# Com.net
KiCad netlist of a schematic drawn in Altium Designer
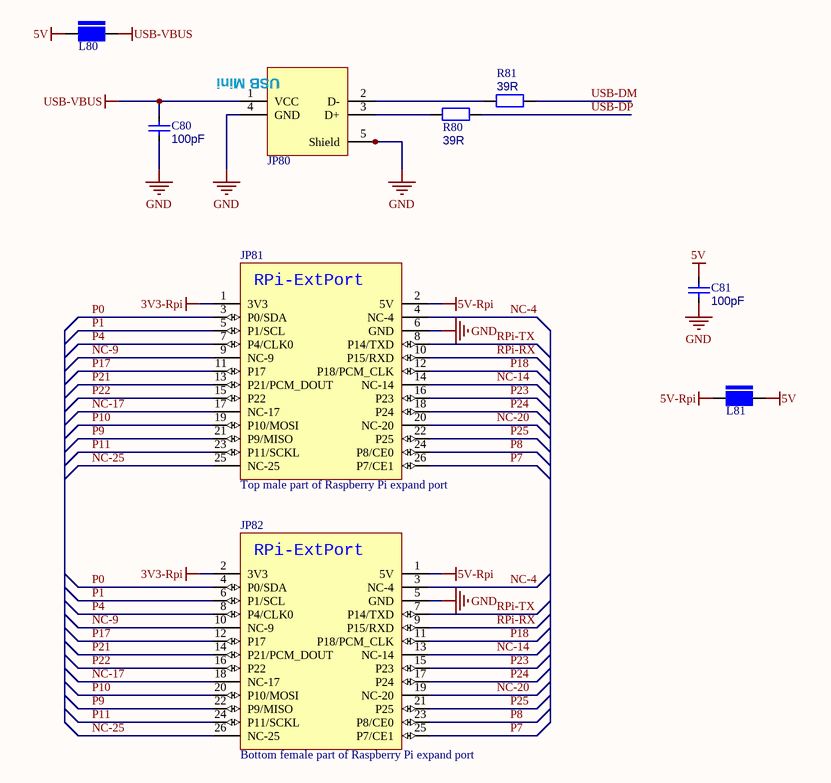
[diagram p0: Com.SchDoc]

(export (version "E")
  (design (tool "Eeschema 10.0.6"))
  (components
    (comp (ref "C80")
      (value "100pF")
      (footprint "CC1005-0402")
      (fields (field (name "Comment") "Condensateur"))
      (libsource (lib "Common") (part "Condensateur"))
    )
    (comp (ref "C81")
      (value "100pF")
      (footprint "CC1005-0402")
      (fields (field (name "Comment") "Condensateur"))
      (libsource (lib "Common") (part "Condensateur"))
    )
    (comp (ref "JP80")
      (value "USB Mini-B SMD")
      (footprint "UX60SC-MB-5ST")
      (description "USB Mini, Type B, SMD")
      (libsource (lib "Connectors") (part "USB Mini-B SMD"))
    )
    (comp (ref "JP81")
      (value "Top male part of Raspberry Pi expand port")
      (footprint "2x13 pins SMT male header")
      (libsource (lib "OpenSCB") (part "RPi-ExtPort-Top"))
    )
    (comp (ref "JP82")
      (value "Bottom female part of Raspberry Pi expand port")
      (footprint "2x13 pins SMT female header")
      (libsource (lib "OpenSCB") (part "RPi-ExtPort-Bottom"))
    )
    (comp (ref "L80")
      (value "Ferrite")
      (footprint "CR1608-0603")
      (description "Ferrite CMS")
      (libsource (lib "Common") (part "Ferrite"))
    )
    (comp (ref "L81")
      (value "Ferrite")
      (footprint "CR1608-0603")
      (description "Ferrite CMS")
      (libsource (lib "Common") (part "Ferrite"))
    )
    (comp (ref "R80")
      (value "39R")
      (footprint "CR1005-0402")
      (fields (field (name "POWER") "0.5W") (field (name "Comment") "Resistance"))
      (libsource (lib "Common") (part "Resistance"))
    )
    (comp (ref "R81")
      (value "39R")
      (footprint "CR1005-0402")
      (fields (field (name "POWER") "0.5W") (field (name "Comment") "Resistance"))
      (libsource (lib "Common") (part "Resistance"))
    )
  )
  (nets
    (net (code "1") (name "/NC-4") (class "Default")
      (node (ref "JP81") (pin "4") (pinfunction "NC-4_4") (pintype "passive"))
      (node (ref "JP82") (pin "3") (pinfunction "NC-4_3") (pintype "passive"))
    )
    (net (code "2") (name "/NC-9") (class "Default")
      (node (ref "JP81") (pin "9") (pinfunction "NC-9_9") (pintype "passive"))
      (node (ref "JP82") (pin "10") (pinfunction "NC-9_10") (pintype "passive"))
    )
    (net (code "3") (name "/NC-14") (class "Default")
      (node (ref "JP81") (pin "14") (pinfunction "NC-14_14") (pintype "passive"))
      (node (ref "JP82") (pin "13") (pinfunction "NC-14_13") (pintype "passive"))
    )
    (net (code "4") (name "/NC-17") (class "Default")
      (node (ref "JP81") (pin "17") (pinfunction "NC-17_17") (pintype "passive"))
      (node (ref "JP82") (pin "18") (pinfunction "NC-17_18") (pintype "passive"))
    )
    (net (code "5") (name "/NC-20") (class "Default")
      (node (ref "JP81") (pin "20") (pinfunction "NC-20_20") (pintype "passive"))
      (node (ref "JP82") (pin "19") (pinfunction "NC-20_19") (pintype "passive"))
    )
    (net (code "6") (name "/NC-25") (class "Default")
      (node (ref "JP81") (pin "25") (pinfunction "NC-25_25") (pintype "passive"))
      (node (ref "JP82") (pin "26") (pinfunction "NC-25_26") (pintype "passive"))
    )
    (net (code "7") (name "/P0") (class "Default")
      (node (ref "JP81") (pin "3") (pinfunction "P0/SDA_3") (pintype "bidirectional"))
      (node (ref "JP82") (pin "4") (pinfunction "P0/SDA_4") (pintype "bidirectional"))
    )
    (net (code "8") (name "/P1") (class "Default")
      (node (ref "JP81") (pin "5") (pinfunction "P1/SCL_5") (pintype "bidirectional"))
      (node (ref "JP82") (pin "6") (pinfunction "P1/SCL_6") (pintype "bidirectional"))
    )
    (net (code "9") (name "/P4") (class "Default")
      (node (ref "JP81") (pin "7") (pinfunction "P4/CLK0_7") (pintype "bidirectional"))
      (node (ref "JP82") (pin "8") (pinfunction "P4/CLK0_8") (pintype "bidirectional"))
    )
    (net (code "10") (name "/P7") (class "Default")
      (node (ref "JP81") (pin "26") (pinfunction "P7/CE1_26") (pintype "bidirectional"))
      (node (ref "JP82") (pin "25") (pinfunction "P7/CE1_25") (pintype "bidirectional"))
    )
    (net (code "11") (name "/P8") (class "Default")
      (node (ref "JP81") (pin "24") (pinfunction "P8/CE0_24") (pintype "bidirectional"))
      (node (ref "JP82") (pin "23") (pinfunction "P8/CE0_23") (pintype "bidirectional"))
    )
    (net (code "12") (name "/P9") (class "Default")
      (node (ref "JP81") (pin "21") (pinfunction "P9/MISO_21") (pintype "bidirectional"))
      (node (ref "JP82") (pin "22") (pinfunction "P9/MISO_22") (pintype "bidirectional"))
    )
    (net (code "13") (name "/P10") (class "Default")
      (node (ref "JP81") (pin "19") (pinfunction "P10/MOSI_19") (pintype "bidirectional"))
      (node (ref "JP82") (pin "20") (pinfunction "P10/MOSI_20") (pintype "bidirectional"))
    )
    (net (code "14") (name "/P11") (class "Default")
      (node (ref "JP81") (pin "23") (pinfunction "P11/SCKL_23") (pintype "bidirectional"))
      (node (ref "JP82") (pin "24") (pinfunction "P11/SCKL_24") (pintype "bidirectional"))
    )
    (net (code "15") (name "/P17") (class "Default")
      (node (ref "JP81") (pin "11") (pinfunction "P17_11") (pintype "bidirectional"))
      (node (ref "JP82") (pin "12") (pinfunction "P17_12") (pintype "bidirectional"))
    )
    (net (code "16") (name "/P18") (class "Default")
      (node (ref "JP81") (pin "12") (pinfunction "P18/PCM_CLK_12") (pintype "bidirectional"))
      (node (ref "JP82") (pin "11") (pinfunction "P18/PCM_CLK_11") (pintype "bidirectional"))
    )
    (net (code "17") (name "/P21") (class "Default")
      (node (ref "JP81") (pin "13") (pinfunction "P21/PCM_DOUT_13") (pintype "bidirectional"))
      (node (ref "JP82") (pin "14") (pinfunction "P21/PCM_DOUT_14") (pintype "bidirectional"))
    )
    (net (code "18") (name "/P22") (class "Default")
      (node (ref "JP81") (pin "15") (pinfunction "P22_15") (pintype "bidirectional"))
      (node (ref "JP82") (pin "16") (pinfunction "P22_16") (pintype "bidirectional"))
    )
    (net (code "19") (name "/P23") (class "Default")
      (node (ref "JP81") (pin "16") (pinfunction "P23_16") (pintype "bidirectional"))
      (node (ref "JP82") (pin "15") (pinfunction "P23_15") (pintype "bidirectional"))
    )
    (net (code "20") (name "/P24") (class "Default")
      (node (ref "JP81") (pin "18") (pinfunction "P24_18") (pintype "bidirectional"))
      (node (ref "JP82") (pin "17") (pinfunction "P24_17") (pintype "bidirectional"))
    )
    (net (code "21") (name "/P25") (class "Default")
      (node (ref "JP81") (pin "22") (pinfunction "P25_22") (pintype "bidirectional"))
      (node (ref "JP82") (pin "21") (pinfunction "P25_21") (pintype "bidirectional"))
    )
    (net (code "22") (name "/RPi-RX") (class "Default")
      (node (ref "JP81") (pin "10") (pinfunction "P15/RXD_10") (pintype "bidirectional"))
      (node (ref "JP82") (pin "9") (pinfunction "P15/RXD_9") (pintype "bidirectional"))
    )
    (net (code "23") (name "/RPi-TX") (class "Default")
      (node (ref "JP81") (pin "8") (pinfunction "P14/TXD_8") (pintype "bidirectional"))
      (node (ref "JP82") (pin "7") (pinfunction "P14/TXD_7") (pintype "bidirectional"))
    )
    (net (code "24") (name "/USB-DM") (class "Default")
      (node (ref "R81") (pin "2") (pinfunction "2_2") (pintype "passive"))
    )
    (net (code "25") (name "/USB-DP") (class "Default")
      (node (ref "R80") (pin "2") (pinfunction "2_2") (pintype "passive"))
    )
    (net (code "26") (name "3V3-Rpi") (class "Default")
      (node (ref "JP81") (pin "1") (pinfunction "3V3_1") (pintype "power_in"))
      (node (ref "JP82") (pin "2") (pinfunction "3V3_2") (pintype "power_in"))
    )
    (net (code "27") (name "5V") (class "Default")
      (node (ref "C81") (pin "2") (pinfunction "2_2") (pintype "passive"))
      (node (ref "L80") (pin "1") (pinfunction "1_1") (pintype "passive"))
      (node (ref "L81") (pin "2") (pinfunction "2_2") (pintype "passive"))
    )
    (net (code "28") (name "5V-Rpi") (class "Default")
      (node (ref "JP81") (pin "2") (pinfunction "5V_2") (pintype "power_in"))
      (node (ref "JP82") (pin "1") (pinfunction "5V_1") (pintype "power_in"))
      (node (ref "L81") (pin "1") (pinfunction "1_1") (pintype "passive"))
    )
    (net (code "29") (name "GND") (class "Default")
      (node (ref "C80") (pin "1") (pinfunction "1_1") (pintype "passive"))
      (node (ref "C81") (pin "1") (pinfunction "1_1") (pintype "passive"))
      (node (ref "JP80") (pin "4") (pinfunction "GND_4") (pintype "power_in"))
      (node (ref "JP80") (pin "5") (pinfunction "Shield_5") (pintype "power_in"))
      (node (ref "JP80") (pin "6") (pinfunction "Shield_6") (pintype "passive"))
      (node (ref "JP80") (pin "7") (pinfunction "Shield_7") (pintype "passive"))
      (node (ref "JP81") (pin "6") (pinfunction "GND_6") (pintype "power_in"))
      (node (ref "JP82") (pin "5") (pinfunction "GND_5") (pintype "power_in"))
    )
    (net (code "30") (name "Net-(JP80-D+)") (class "Default")
      (node (ref "JP80") (pin "3") (pinfunction "D+_3") (pintype "passive"))
      (node (ref "R80") (pin "1") (pinfunction "1_1") (pintype "passive"))
    )
    (net (code "31") (name "Net-(JP80-D-)") (class "Default")
      (node (ref "JP80") (pin "2") (pinfunction "D-_2") (pintype "passive"))
      (node (ref "R81") (pin "1") (pinfunction "1_1") (pintype "passive"))
    )
    (net (code "32") (name "USB-VBUS") (class "Default")
      (node (ref "C80") (pin "2") (pinfunction "2_2") (pintype "passive"))
      (node (ref "JP80") (pin "1") (pinfunction "VCC_1") (pintype "power_in"))
      (node (ref "L80") (pin "2") (pinfunction "2_2") (pintype "passive"))
    )
  )
)
